# ICSP_Inline_Pogo.net
KiCad netlist of a schematic drawn in EAGLE
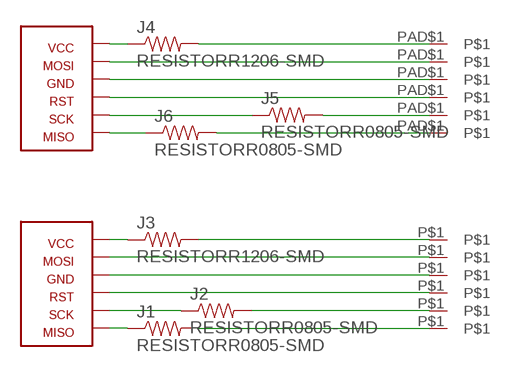
[diagram p0: schematic, sheet 1]

(export (version "E")
  (design (tool "Eeschema 10.0.6"))
  (components
    (comp (ref "GND")
      (value "POGO_PADR50")
      (footprint "eagle-import:P50_POGO_PIN")
      (libsource (lib "eagle-import") (part "POGO_PADR50"))
    )
    (comp (ref "GND1")
      (value "POGO_PADR75")
      (footprint "eagle-import:P75_POGO_PIN")
      (libsource (lib "eagle-import") (part "POGO_PADR75"))
    )
    (comp (ref "J1")
      (value "RESISTORR0805-SMD")
      (footprint "eagle-import:R0805")
      (libsource (lib "eagle-import") (part "RESISTORR0805-SMD"))
    )
    (comp (ref "J2")
      (value "RESISTORR0805-SMD")
      (footprint "eagle-import:R0805")
      (libsource (lib "eagle-import") (part "RESISTORR0805-SMD"))
    )
    (comp (ref "J3")
      (value "RESISTORR1206-SMD")
      (footprint "eagle-import:R1206")
      (libsource (lib "eagle-import") (part "RESISTORR1206-SMD"))
    )
    (comp (ref "J4")
      (value "RESISTORR1206-SMD")
      (footprint "eagle-import:R1206")
      (libsource (lib "eagle-import") (part "RESISTORR1206-SMD"))
    )
    (comp (ref "J5")
      (value "RESISTORR0805-SMD")
      (footprint "eagle-import:R0805")
      (libsource (lib "eagle-import") (part "RESISTORR0805-SMD"))
    )
    (comp (ref "J6")
      (value "RESISTORR0805-SMD")
      (footprint "eagle-import:R0805")
      (libsource (lib "eagle-import") (part "RESISTORR0805-SMD"))
    )
    (comp (ref "MISO")
      (value "POGO_PADR50")
      (footprint "eagle-import:P50_POGO_PIN")
      (libsource (lib "eagle-import") (part "POGO_PADR50"))
    )
    (comp (ref "MISO1")
      (value "POGO_PADR75")
      (footprint "eagle-import:P75_POGO_PIN")
      (libsource (lib "eagle-import") (part "POGO_PADR75"))
    )
    (comp (ref "MOSI")
      (value "POGO_PADR50")
      (footprint "eagle-import:P50_POGO_PIN")
      (libsource (lib "eagle-import") (part "POGO_PADR50"))
    )
    (comp (ref "MOSI1")
      (value "POGO_PADR75")
      (footprint "eagle-import:P75_POGO_PIN")
      (libsource (lib "eagle-import") (part "POGO_PADR75"))
    )
    (comp (ref "RST")
      (value "POGO_PADR50")
      (footprint "eagle-import:P50_POGO_PIN")
      (libsource (lib "eagle-import") (part "POGO_PADR50"))
    )
    (comp (ref "RST1")
      (value "POGO_PADR75")
      (footprint "eagle-import:P75_POGO_PIN")
      (libsource (lib "eagle-import") (part "POGO_PADR75"))
    )
    (comp (ref "SCK")
      (value "POGO_PADR50")
      (footprint "eagle-import:P50_POGO_PIN")
      (libsource (lib "eagle-import") (part "POGO_PADR50"))
    )
    (comp (ref "SCK1")
      (value "POGO_PADR75")
      (footprint "eagle-import:P75_POGO_PIN")
      (libsource (lib "eagle-import") (part "POGO_PADR75"))
    )
    (comp (ref "U$1")
      (value "AVR_ICSP_6P2X3_THP")
      (footprint "eagle-import:AVR_ICSP_2X3_THP")
      (libsource (lib "eagle-import") (part "AVR_ICSP_6P2X3_THP"))
    )
    (comp (ref "U$3")
      (value "AVR_ICSP_6P2X3_THP")
      (footprint "eagle-import:AVR_ICSP_2X3_THP")
      (libsource (lib "eagle-import") (part "AVR_ICSP_6P2X3_THP"))
    )
    (comp (ref "VCC")
      (value "POGO_PADR50")
      (footprint "eagle-import:P50_POGO_PIN")
      (libsource (lib "eagle-import") (part "POGO_PADR50"))
    )
    (comp (ref "VCC1")
      (value "POGO_PADR75")
      (footprint "eagle-import:P75_POGO_PIN")
      (libsource (lib "eagle-import") (part "POGO_PADR75"))
    )
  )
  (nets
    (net (code "1") (name "Net-(GND-PadP$1)") (class "Default")
      (node (ref "GND") (pin "P$1") (pinfunction "P$1_P$1") (pintype "bidirectional"))
      (node (ref "U$3") (pin "GND") (pinfunction "GND_GND") (pintype "bidirectional"))
    )
    (net (code "2") (name "Net-(GND1-P$1)") (class "Default")
      (node (ref "GND1") (pin "PAD$1") (pinfunction "P$1_PAD$1") (pintype "bidirectional"))
      (node (ref "U$1") (pin "GND") (pinfunction "GND_GND") (pintype "bidirectional"))
    )
    (net (code "3") (name "Net-(J1-Pad1)") (class "Default")
      (node (ref "J1") (pin "1") (pinfunction "1_1") (pintype "passive"))
      (node (ref "U$3") (pin "MISO") (pinfunction "MISO_MISO") (pintype "bidirectional"))
    )
    (net (code "4") (name "Net-(J1-Pad2)") (class "Default")
      (node (ref "J1") (pin "2") (pinfunction "2_2") (pintype "passive"))
      (node (ref "MISO") (pin "P$1") (pinfunction "P$1_P$1") (pintype "bidirectional"))
    )
    (net (code "5") (name "Net-(J2-Pad1)") (class "Default")
      (node (ref "J2") (pin "1") (pinfunction "1_1") (pintype "passive"))
      (node (ref "U$3") (pin "SCK") (pinfunction "SCK_SCK") (pintype "bidirectional"))
    )
    (net (code "6") (name "Net-(J2-Pad2)") (class "Default")
      (node (ref "J2") (pin "2") (pinfunction "2_2") (pintype "passive"))
      (node (ref "SCK") (pin "P$1") (pinfunction "P$1_P$1") (pintype "bidirectional"))
    )
    (net (code "7") (name "Net-(J3-Pad1)") (class "Default")
      (node (ref "J3") (pin "1") (pinfunction "1_1") (pintype "passive"))
      (node (ref "U$3") (pin "VCC") (pinfunction "VCC_VCC") (pintype "bidirectional"))
    )
    (net (code "8") (name "Net-(J3-Pad2)") (class "Default")
      (node (ref "J3") (pin "2") (pinfunction "2_2") (pintype "passive"))
      (node (ref "VCC") (pin "P$1") (pinfunction "P$1_P$1") (pintype "bidirectional"))
    )
    (net (code "9") (name "Net-(J4-Pad1)") (class "Default")
      (node (ref "J4") (pin "1") (pinfunction "1_1") (pintype "passive"))
      (node (ref "U$1") (pin "VCC") (pinfunction "VCC_VCC") (pintype "bidirectional"))
    )
    (net (code "10") (name "Net-(J5-Pad1)") (class "Default")
      (node (ref "J5") (pin "1") (pinfunction "1_1") (pintype "passive"))
      (node (ref "U$1") (pin "SCK") (pinfunction "SCK_SCK") (pintype "bidirectional"))
    )
    (net (code "11") (name "Net-(J6-Pad1)") (class "Default")
      (node (ref "J6") (pin "1") (pinfunction "1_1") (pintype "passive"))
      (node (ref "U$1") (pin "MISO") (pinfunction "MISO_MISO") (pintype "bidirectional"))
    )
    (net (code "12") (name "Net-(MISO1-P$1)") (class "Default")
      (node (ref "J6") (pin "2") (pinfunction "2_2") (pintype "passive"))
      (node (ref "MISO1") (pin "PAD$1") (pinfunction "P$1_PAD$1") (pintype "bidirectional"))
    )
    (net (code "13") (name "Net-(MOSI-PadP$1)") (class "Default")
      (node (ref "MOSI") (pin "P$1") (pinfunction "P$1_P$1") (pintype "bidirectional"))
      (node (ref "U$3") (pin "MOSI") (pinfunction "MOSI_MOSI") (pintype "bidirectional"))
    )
    (net (code "14") (name "Net-(MOSI1-P$1)") (class "Default")
      (node (ref "MOSI1") (pin "PAD$1") (pinfunction "P$1_PAD$1") (pintype "bidirectional"))
      (node (ref "U$1") (pin "MOSI") (pinfunction "MOSI_MOSI") (pintype "bidirectional"))
    )
    (net (code "15") (name "Net-(RST-PadP$1)") (class "Default")
      (node (ref "RST") (pin "P$1") (pinfunction "P$1_P$1") (pintype "bidirectional"))
      (node (ref "U$3") (pin "RST") (pinfunction "RST_RST") (pintype "bidirectional"))
    )
    (net (code "16") (name "Net-(RST1-P$1)") (class "Default")
      (node (ref "RST1") (pin "PAD$1") (pinfunction "P$1_PAD$1") (pintype "bidirectional"))
      (node (ref "U$1") (pin "RST") (pinfunction "RST_RST") (pintype "bidirectional"))
    )
    (net (code "17") (name "Net-(SCK1-P$1)") (class "Default")
      (node (ref "J5") (pin "2") (pinfunction "2_2") (pintype "passive"))
      (node (ref "SCK1") (pin "PAD$1") (pinfunction "P$1_PAD$1") (pintype "bidirectional"))
    )
    (net (code "18") (name "Net-(VCC1-P$1)") (class "Default")
      (node (ref "J4") (pin "2") (pinfunction "2_2") (pintype "passive"))
      (node (ref "VCC1") (pin "PAD$1") (pinfunction "P$1_PAD$1") (pintype "bidirectional"))
    )
  )
)
